# battery_box.net
KiCad netlist of a schematic drawn in EAGLE
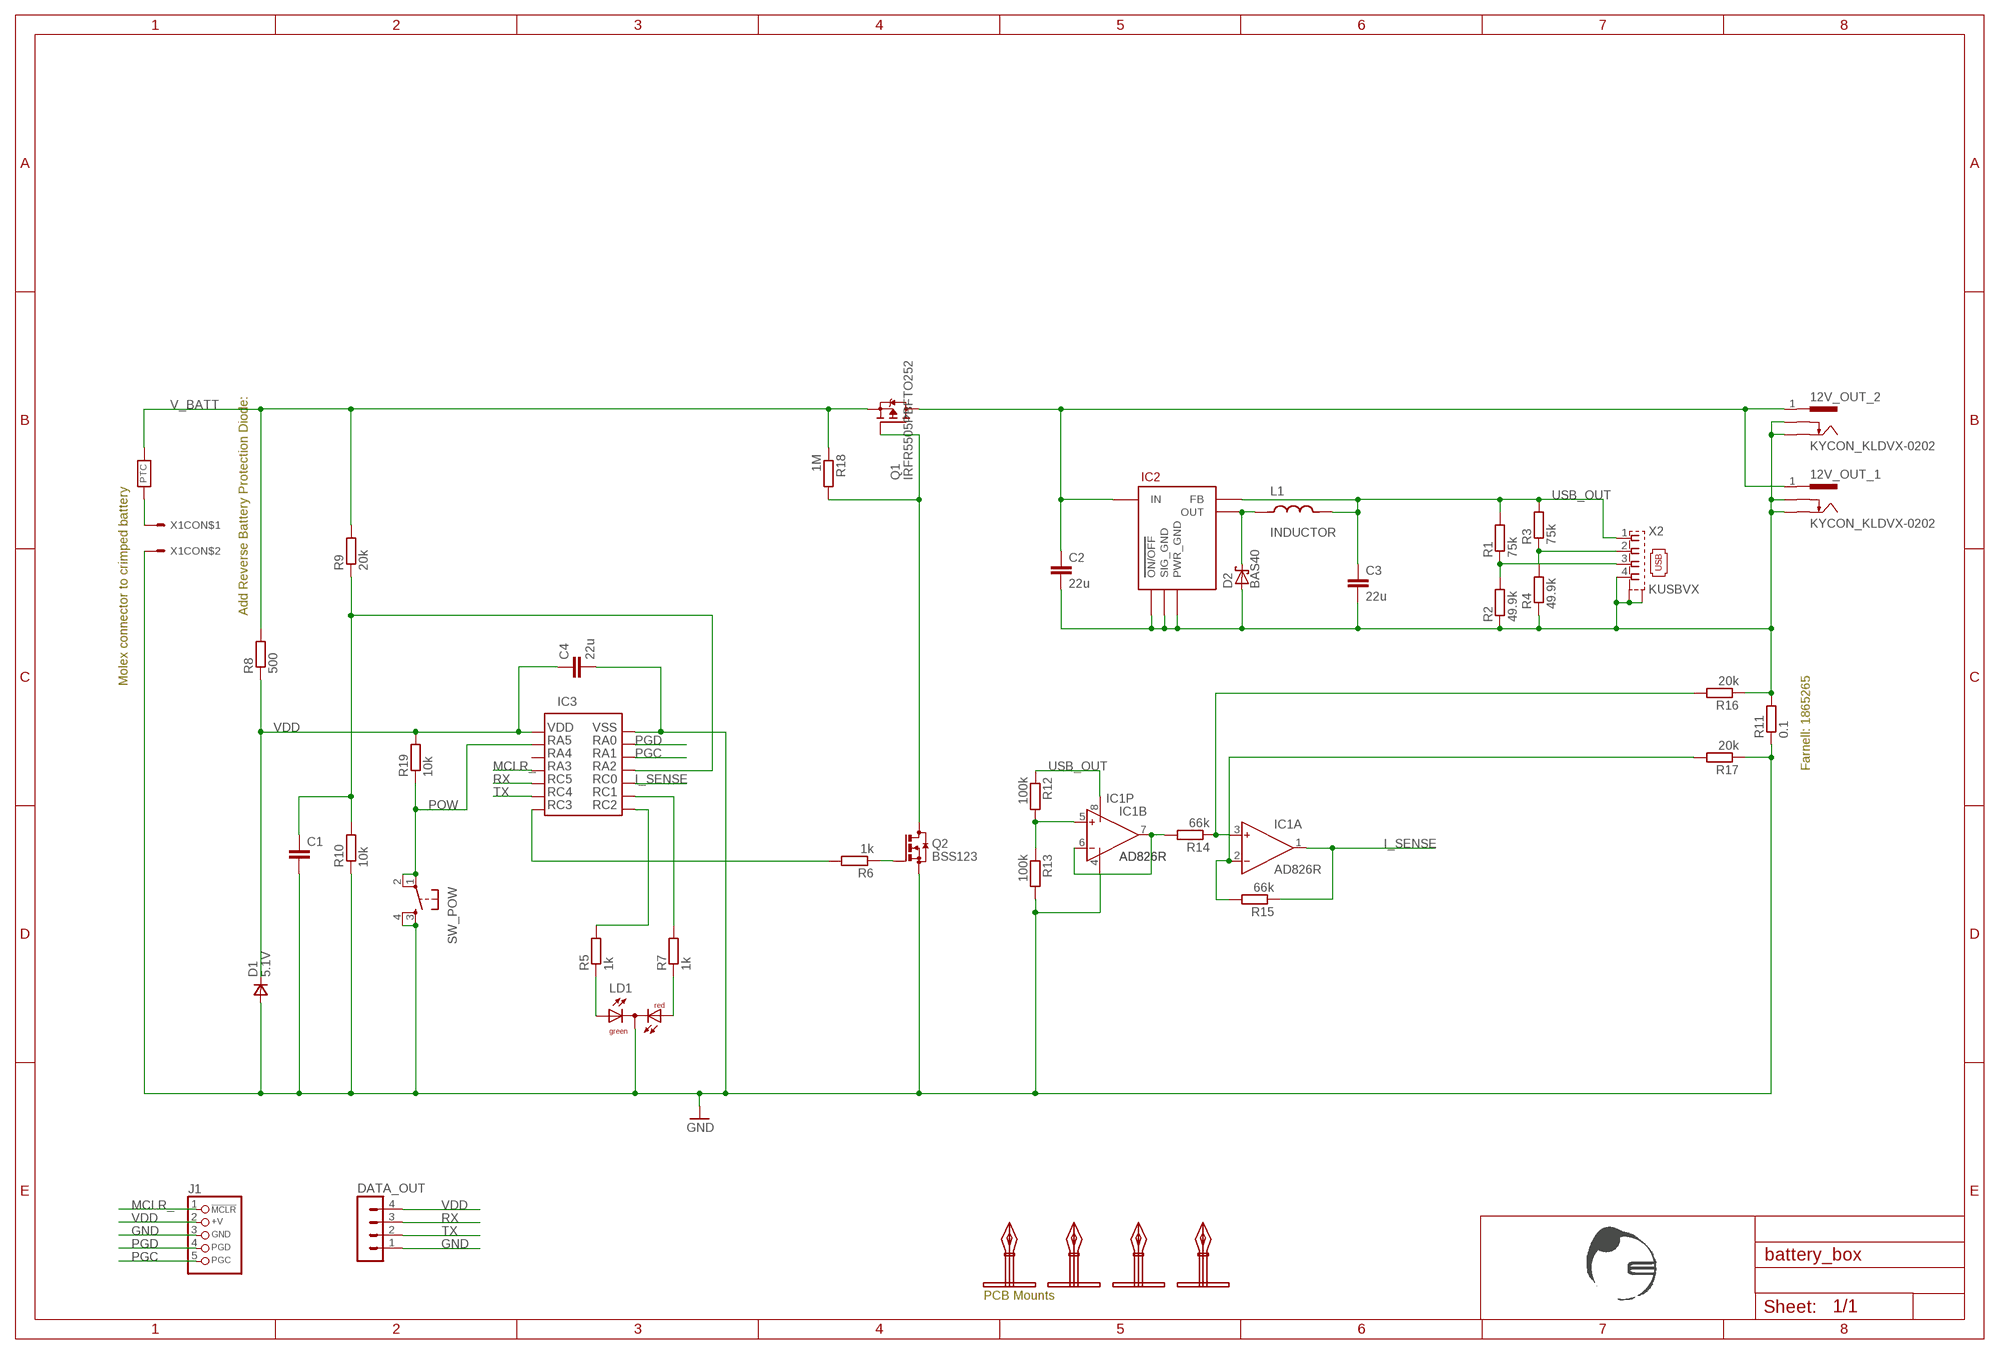
[diagram p0: schematic, sheet 1]

(export (version "E")
  (design (tool "Eeschema 10.0.6"))
  (components
    (comp (ref "12V_OUT_1")
      (value "KYCON_KLDVX-0202")
      (footprint "eagle-import:KYCON_KLVDX_2020_B")
      (libsource (lib "eagle-import") (part "KYCON_KLDVX-0202"))
    )
    (comp (ref "12V_OUT_2")
      (value "KYCON_KLDVX-0202")
      (footprint "eagle-import:KYCON_KLVDX_2020_B")
      (libsource (lib "eagle-import") (part "KYCON_KLDVX-0202"))
    )
    (comp (ref "C1")
      (value "C-EUC0805")
      (footprint "eagle-import:C0805")
      (libsource (lib "eagle-import") (part "C-EUC0805"))
    )
    (comp (ref "C2")
      (value "22u")
      (footprint "eagle-import:C0805")
      (libsource (lib "eagle-import") (part "C-EUC0805"))
    )
    (comp (ref "C3")
      (value "22u")
      (footprint "eagle-import:C0805")
      (libsource (lib "eagle-import") (part "C-EUC0805"))
    )
    (comp (ref "C4")
      (value "22u")
      (footprint "eagle-import:C0805")
      (libsource (lib "eagle-import") (part "C-EUC0805"))
    )
    (comp (ref "D1")
      (value "5.1V")
      (footprint "eagle-import:SOD323")
      (fields (field (name "MPN") "CDSOD323-T05C"))
      (libsource (lib "eagle-import") (part "DSOD323"))
    )
    (comp (ref "D2")
      (value "BAS40")
      (footprint "eagle-import:SOT23")
      (libsource (lib "eagle-import") (part "BAS40"))
    )
    (comp (ref "DATA_OUT")
      (value "MA04-1")
      (footprint "eagle-import:MA04-1")
      (libsource (lib "eagle-import") (part "MA04-1"))
    )
    (comp (ref "IC1")
      (value "AD826R")
      (footprint "eagle-import:SO8")
      (libsource (lib "eagle-import") (part "AD826R"))
    )
    (comp (ref "IC2")
      (value "LM2574")
      (footprint "eagle-import:SO14W")
      (libsource (lib "eagle-import") (part "LM2574"))
    )
    (comp (ref "IC3")
      (value "PIC16F1824")
      (footprint "eagle-import:SO-14")
      (libsource (lib "eagle-import") (part "PIC16F1824"))
    )
    (comp (ref "J1")
      (value "CON_HEADER_PRG_PIC_ICSPA")
      (footprint "eagle-import:HEADER_PRG_1X05")
      (libsource (lib "eagle-import") (part "CON_HEADER_PRG_PIC_ICSPA"))
    )
    (comp (ref "L1")
      (value "INDUCTOR")
      (footprint "eagle-import:SMD_INDUCTOR")
      (libsource (lib "eagle-import") (part "INDUCTOR"))
    )
    (comp (ref "LD1")
      (value "DUOLED-RG-C")
      (footprint "eagle-import:DUOLED-C-5MM")
      (libsource (lib "eagle-import") (part "DUOLED-RG-C"))
    )
    (comp (ref "Q1")
      (value "IRFR5505PBFTO252")
      (footprint "eagle-import:TO252")
      (libsource (lib "eagle-import") (part "IRFR5505PBFTO252"))
    )
    (comp (ref "Q2")
      (value "BSS123")
      (footprint "eagle-import:SOT23")
      (libsource (lib "eagle-import") (part "BSS123"))
    )
    (comp (ref "R1")
      (value "75k")
      (footprint "eagle-import:R0805")
      (libsource (lib "eagle-import") (part "R-EU_R0805"))
    )
    (comp (ref "R2")
      (value "49.9k")
      (footprint "eagle-import:R0805")
      (libsource (lib "eagle-import") (part "R-EU_R0805"))
    )
    (comp (ref "R3")
      (value "75k")
      (footprint "eagle-import:R0805")
      (libsource (lib "eagle-import") (part "R-EU_R0805"))
    )
    (comp (ref "R4")
      (value "49.9k")
      (footprint "eagle-import:R0805")
      (libsource (lib "eagle-import") (part "R-EU_R0805"))
    )
    (comp (ref "R5")
      (value "1k")
      (footprint "eagle-import:R0805")
      (libsource (lib "eagle-import") (part "R-EU_R0805"))
    )
    (comp (ref "R6")
      (value "1k")
      (footprint "eagle-import:R0805")
      (libsource (lib "eagle-import") (part "R-EU_R0805"))
    )
    (comp (ref "R7")
      (value "1k")
      (footprint "eagle-import:R0805")
      (libsource (lib "eagle-import") (part "R-EU_R0805"))
    )
    (comp (ref "R8")
      (value "500")
      (footprint "eagle-import:R0805")
      (libsource (lib "eagle-import") (part "R-EU_R0805"))
    )
    (comp (ref "R9")
      (value "20k")
      (footprint "eagle-import:R0805")
      (libsource (lib "eagle-import") (part "R-EU_R0805"))
    )
    (comp (ref "R10")
      (value "10k")
      (footprint "eagle-import:R0805")
      (libsource (lib "eagle-import") (part "R-EU_R0805"))
    )
    (comp (ref "R11")
      (value "0.1")
      (footprint "eagle-import:R2512")
      (libsource (lib "eagle-import") (part "R-EU_R2512"))
    )
    (comp (ref "R12")
      (value "100k")
      (footprint "eagle-import:R0805")
      (libsource (lib "eagle-import") (part "R-EU_R0805"))
    )
    (comp (ref "R13")
      (value "100k")
      (footprint "eagle-import:R0805")
      (libsource (lib "eagle-import") (part "R-EU_R0805"))
    )
    (comp (ref "R14")
      (value "66k")
      (footprint "eagle-import:R0805")
      (libsource (lib "eagle-import") (part "R-EU_R0805"))
    )
    (comp (ref "R15")
      (value "66k")
      (footprint "eagle-import:R0805")
      (libsource (lib "eagle-import") (part "R-EU_R0805"))
    )
    (comp (ref "R16")
      (value "20k")
      (footprint "eagle-import:R0805")
      (libsource (lib "eagle-import") (part "R-EU_R0805"))
    )
    (comp (ref "R17")
      (value "20k")
      (footprint "eagle-import:R0805")
      (libsource (lib "eagle-import") (part "R-EU_R0805"))
    )
    (comp (ref "R18")
      (value "1M")
      (footprint "eagle-import:R0805")
      (libsource (lib "eagle-import") (part "R-EU_R0805"))
    )
    (comp (ref "R19")
      (value "10k")
      (footprint "eagle-import:R0805")
      (libsource (lib "eagle-import") (part "R-EU_R0805"))
    )
    (comp (ref "SW_POW")
      (value "TAC_SWITCHPTH")
      (footprint "eagle-import:TACTILE-PTH")
      (libsource (lib "eagle-import") (part "TAC_SWITCHPTH"))
    )
    (comp (ref "U$1")
      (value "EQUINOX_LOGO_SMALL")
      (footprint "eagle-import:EQUINOX_LOGO_SMALL")
      (libsource (lib "eagle-import") (part "EQUINOX_LOGO_SMALL"))
    )
    (comp (ref "U$2")
      (value "PTC")
      (footprint "eagle-import:MINISMDC260F")
      (libsource (lib "eagle-import") (part "PTC"))
    )
    (comp (ref "U$5")
      (value "PCB_MOUNT_RICHO")
      (footprint "eagle-import:PCBMOUNT")
      (libsource (lib "eagle-import") (part "PCB_MOUNT_RICHO"))
    )
    (comp (ref "U$6")
      (value "PCB_MOUNT_RICHO")
      (footprint "eagle-import:PCBMOUNT")
      (libsource (lib "eagle-import") (part "PCB_MOUNT_RICHO"))
    )
    (comp (ref "U$7")
      (value "PCB_MOUNT_RICHO")
      (footprint "eagle-import:PCBMOUNT")
      (libsource (lib "eagle-import") (part "PCB_MOUNT_RICHO"))
    )
    (comp (ref "U$8")
      (value "PCB_MOUNT_RICHO")
      (footprint "eagle-import:PCBMOUNT")
      (libsource (lib "eagle-import") (part "PCB_MOUNT_RICHO"))
    )
    (comp (ref "X1")
      (value "CON_MOLEX_39_29_1028")
      (footprint "eagle-import:MOLEX_39_29_1028")
      (libsource (lib "eagle-import") (part "CON_MOLEX_39_29_1028"))
    )
    (comp (ref "X2")
      (value "KUSBVX")
      (footprint "eagle-import:KUSBVX")
      (libsource (lib "eagle-import") (part "KUSBVX"))
    )
  )
  (nets
    (net (code "1") (name "/I_SENSE") (class "Default")
      (node (ref "IC1") (pin "1") (pinfunction "OUT_1") (pintype "output"))
      (node (ref "IC3") (pin "10") (pinfunction "P$10_10") (pintype "bidirectional"))
      (node (ref "R15") (pin "1") (pinfunction "1_1") (pintype "passive"))
    )
    (net (code "2") (name "/MCLR_") (class "Default")
      (node (ref "IC3") (pin "4") (pinfunction "P$4_4") (pintype "bidirectional"))
      (node (ref "J1") (pin "1") (pinfunction "/MCLR_1") (pintype "passive"))
    )
    (net (code "3") (name "/PGC") (class "Default")
      (node (ref "IC3") (pin "12") (pinfunction "P$12_12") (pintype "bidirectional"))
      (node (ref "J1") (pin "5") (pinfunction "PGC_5") (pintype "passive"))
    )
    (net (code "4") (name "/PGD") (class "Default")
      (node (ref "IC3") (pin "13") (pinfunction "P$13_13") (pintype "bidirectional"))
      (node (ref "J1") (pin "4") (pinfunction "PGD_4") (pintype "passive"))
    )
    (net (code "5") (name "/POW") (class "Default")
      (node (ref "IC3") (pin "2") (pinfunction "P$2_2") (pintype "bidirectional"))
      (node (ref "R19") (pin "1") (pinfunction "1_1") (pintype "passive"))
      (node (ref "SW_POW") (pin "1") (pinfunction "1_1") (pintype "passive"))
      (node (ref "SW_POW") (pin "2") (pinfunction "2_2") (pintype "passive"))
    )
    (net (code "6") (name "/RX") (class "Default")
      (node (ref "DATA_OUT") (pin "3") (pinfunction "3_3") (pintype "passive"))
      (node (ref "IC3") (pin "5") (pinfunction "P$5_5") (pintype "bidirectional"))
    )
    (net (code "7") (name "/TX") (class "Default")
      (node (ref "DATA_OUT") (pin "2") (pinfunction "2_2") (pintype "passive"))
      (node (ref "IC3") (pin "6") (pinfunction "P$6_6") (pintype "bidirectional"))
    )
    (net (code "8") (name "/USB_OUT") (class "Default")
      (node (ref "C3") (pin "1") (pinfunction "1_1") (pintype "passive"))
      (node (ref "IC1") (pin "8") (pinfunction "V+_8") (pintype "power_in"))
      (node (ref "IC2") (pin "3") (pinfunction "FB_3") (pintype "bidirectional"))
      (node (ref "L1") (pin "P$2") (pinfunction "P$2_P$2") (pintype "bidirectional"))
      (node (ref "R1") (pin "2") (pinfunction "2_2") (pintype "passive"))
      (node (ref "R12") (pin "1") (pinfunction "1_1") (pintype "passive"))
      (node (ref "R3") (pin "2") (pinfunction "2_2") (pintype "passive"))
      (node (ref "X2") (pin "1") (pinfunction "1_1") (pintype "passive"))
    )
    (net (code "9") (name "/VDD") (class "Default")
      (node (ref "C4") (pin "1") (pinfunction "1_1") (pintype "passive"))
      (node (ref "D1") (pin "1") (pinfunction "C_1") (pintype "passive"))
      (node (ref "DATA_OUT") (pin "4") (pinfunction "4_4") (pintype "passive"))
      (node (ref "IC3") (pin "1") (pinfunction "P$1_1") (pintype "bidirectional"))
      (node (ref "J1") (pin "2") (pinfunction "+V_2") (pintype "passive"))
      (node (ref "R19") (pin "2") (pinfunction "2_2") (pintype "passive"))
      (node (ref "R8") (pin "1") (pinfunction "1_1") (pintype "passive"))
    )
    (net (code "10") (name "/V_BATT") (class "Default")
      (node (ref "Q1") (pin "2") (pinfunction "S_2") (pintype "passive"))
      (node (ref "R18") (pin "1") (pinfunction "1_1") (pintype "passive"))
      (node (ref "R8") (pin "2") (pinfunction "2_2") (pintype "passive"))
      (node (ref "R9") (pin "2") (pinfunction "2_2") (pintype "passive"))
      (node (ref "U$2") (pin "P$2") (pinfunction "P$2_P$2") (pintype "bidirectional"))
    )
    (net (code "11") (name "GND") (class "Default")
      (node (ref "C1") (pin "2") (pinfunction "2_2") (pintype "passive"))
      (node (ref "C4") (pin "2") (pinfunction "2_2") (pintype "passive"))
      (node (ref "D1") (pin "2") (pinfunction "A_2") (pintype "passive"))
      (node (ref "DATA_OUT") (pin "1") (pinfunction "1_1") (pintype "passive"))
      (node (ref "IC1") (pin "4") (pinfunction "V-_4") (pintype "power_in"))
      (node (ref "IC3") (pin "14") (pinfunction "P$14_14") (pintype "bidirectional"))
      (node (ref "J1") (pin "3") (pinfunction "GND_3") (pintype "passive"))
      (node (ref "LD1") (pin "C") (pinfunction "C_C") (pintype "passive"))
      (node (ref "Q2") (pin "2") (pinfunction "S_2") (pintype "passive"))
      (node (ref "R10") (pin "1") (pinfunction "1_1") (pintype "passive"))
      (node (ref "R11") (pin "1") (pinfunction "1_1") (pintype "passive"))
      (node (ref "R13") (pin "2") (pinfunction "2_2") (pintype "passive"))
      (node (ref "R17") (pin "1") (pinfunction "1_1") (pintype "passive"))
      (node (ref "SW_POW") (pin "3") (pinfunction "3_3") (pintype "passive"))
      (node (ref "SW_POW") (pin "4") (pinfunction "4_4") (pintype "passive"))
      (node (ref "X1") (pin "P$2") (pinfunction "S_P$2") (pintype "passive"))
    )
    (net (code "12") (name "Net-(12V_OUT_1-PAD1)") (class "Default")
      (node (ref "12V_OUT_1") (pin "1") (pinfunction "PAD1_1") (pintype "passive"))
      (node (ref "12V_OUT_2") (pin "1") (pinfunction "PAD1_1") (pintype "passive"))
      (node (ref "C2") (pin "1") (pinfunction "1_1") (pintype "passive"))
      (node (ref "IC2") (pin "10") (pinfunction "IN_10") (pintype "bidirectional"))
      (node (ref "Q1") (pin "3") (pinfunction "D_3") (pintype "passive"))
    )
    (net (code "13") (name "Net-(12V_OUT_1-PAD2)") (class "Default")
      (node (ref "12V_OUT_1") (pin "2") (pinfunction "PAD2_2") (pintype "passive"))
      (node (ref "12V_OUT_1") (pin "3") (pinfunction "PAD3_3") (pintype "passive"))
      (node (ref "12V_OUT_2") (pin "2") (pinfunction "PAD2_2") (pintype "passive"))
      (node (ref "12V_OUT_2") (pin "3") (pinfunction "PAD3_3") (pintype "passive"))
      (node (ref "C2") (pin "2") (pinfunction "2_2") (pintype "passive"))
      (node (ref "C3") (pin "2") (pinfunction "2_2") (pintype "passive"))
      (node (ref "D2") (pin "1") (pinfunction "A_1") (pintype "passive"))
      (node (ref "IC2") (pin "4") (pinfunction "SIG_GND_4") (pintype "bidirectional"))
      (node (ref "IC2") (pin "5") (pinfunction "ON/OFF_5") (pintype "bidirectional"))
      (node (ref "IC2") (pin "6") (pinfunction "PWR_GND_6") (pintype "bidirectional"))
      (node (ref "R11") (pin "2") (pinfunction "2_2") (pintype "passive"))
      (node (ref "R16") (pin "1") (pinfunction "1_1") (pintype "passive"))
      (node (ref "R2") (pin "1") (pinfunction "1_1") (pintype "passive"))
      (node (ref "R4") (pin "1") (pinfunction "1_1") (pintype "passive"))
      (node (ref "X2") (pin "4") (pinfunction "4_4") (pintype "passive"))
      (node (ref "X2") (pin "M1") (pinfunction "S1_M1") (pintype "passive"))
      (node (ref "X2") (pin "M2") (pinfunction "S2_M2") (pintype "passive"))
    )
    (net (code "14") (name "Net-(D2-C)") (class "Default")
      (node (ref "D2") (pin "3") (pinfunction "C_3") (pintype "passive"))
      (node (ref "IC2") (pin "12") (pinfunction "OUT_12") (pintype "bidirectional"))
      (node (ref "L1") (pin "P$1") (pinfunction "P$1_P$1") (pintype "bidirectional"))
    )
    (net (code "15") (name "Net-(IC1A-IN+)") (class "Default")
      (node (ref "IC1") (pin "3") (pinfunction "IN+_3") (pintype "input"))
      (node (ref "R14") (pin "1") (pinfunction "1_1") (pintype "passive"))
      (node (ref "R16") (pin "2") (pinfunction "2_2") (pintype "passive"))
    )
    (net (code "16") (name "Net-(IC1A-IN-)") (class "Default")
      (node (ref "IC1") (pin "2") (pinfunction "IN-_2") (pintype "input"))
      (node (ref "R15") (pin "2") (pinfunction "2_2") (pintype "passive"))
      (node (ref "R17") (pin "2") (pinfunction "2_2") (pintype "passive"))
    )
    (net (code "17") (name "Net-(IC1B-IN+)") (class "Default")
      (node (ref "IC1") (pin "5") (pinfunction "IN+_5") (pintype "input"))
      (node (ref "R12") (pin "2") (pinfunction "2_2") (pintype "passive"))
      (node (ref "R13") (pin "1") (pinfunction "1_1") (pintype "passive"))
    )
    (net (code "18") (name "Net-(IC1B-IN-)") (class "Default")
      (node (ref "IC1") (pin "6") (pinfunction "IN-_6") (pintype "input"))
      (node (ref "IC1") (pin "7") (pinfunction "OUT_7") (pintype "output"))
      (node (ref "R14") (pin "2") (pinfunction "2_2") (pintype "passive"))
    )
    (net (code "19") (name "Net-(IC3-P$7)") (class "Default")
      (node (ref "IC3") (pin "7") (pinfunction "P$7_7") (pintype "bidirectional"))
      (node (ref "R6") (pin "2") (pinfunction "2_2") (pintype "passive"))
    )
    (net (code "20") (name "Net-(IC3-P$8)") (class "Default")
      (node (ref "IC3") (pin "8") (pinfunction "P$8_8") (pintype "bidirectional"))
      (node (ref "R5") (pin "2") (pinfunction "2_2") (pintype "passive"))
    )
    (net (code "21") (name "Net-(IC3-P$9)") (class "Default")
      (node (ref "IC3") (pin "9") (pinfunction "P$9_9") (pintype "bidirectional"))
      (node (ref "R7") (pin "2") (pinfunction "2_2") (pintype "passive"))
    )
    (net (code "22") (name "Net-(IC3-P$11)") (class "Default")
      (node (ref "C1") (pin "1") (pinfunction "1_1") (pintype "passive"))
      (node (ref "IC3") (pin "11") (pinfunction "P$11_11") (pintype "bidirectional"))
      (node (ref "R10") (pin "2") (pinfunction "2_2") (pintype "passive"))
      (node (ref "R9") (pin "1") (pinfunction "1_1") (pintype "passive"))
    )
    (net (code "23") (name "Net-(LD1-AG)") (class "Default")
      (node (ref "LD1") (pin "AX") (pinfunction "AG_AX") (pintype "passive"))
      (node (ref "R5") (pin "1") (pinfunction "1_1") (pintype "passive"))
    )
    (net (code "24") (name "Net-(LD1-PadAR)") (class "Default")
      (node (ref "LD1") (pin "AR") (pinfunction "AR_AR") (pintype "passive"))
      (node (ref "R7") (pin "1") (pinfunction "1_1") (pintype "passive"))
    )
    (net (code "25") (name "Net-(Q1-G)") (class "Default")
      (node (ref "Q1") (pin "1") (pinfunction "G_1") (pintype "passive"))
      (node (ref "Q2") (pin "3") (pinfunction "D_3") (pintype "passive"))
      (node (ref "R18") (pin "2") (pinfunction "2_2") (pintype "passive"))
    )
    (net (code "26") (name "Net-(Q2-G)") (class "Default")
      (node (ref "Q2") (pin "1") (pinfunction "G_1") (pintype "passive"))
      (node (ref "R6") (pin "1") (pinfunction "1_1") (pintype "passive"))
    )
    (net (code "27") (name "Net-(R1-Pad1)") (class "Default")
      (node (ref "R1") (pin "1") (pinfunction "1_1") (pintype "passive"))
      (node (ref "R2") (pin "2") (pinfunction "2_2") (pintype "passive"))
      (node (ref "X2") (pin "3") (pinfunction "3_3") (pintype "passive"))
    )
    (net (code "28") (name "Net-(R3-Pad1)") (class "Default")
      (node (ref "R3") (pin "1") (pinfunction "1_1") (pintype "passive"))
      (node (ref "R4") (pin "2") (pinfunction "2_2") (pintype "passive"))
      (node (ref "X2") (pin "2") (pinfunction "2_2") (pintype "passive"))
    )
    (net (code "29") (name "Net-(X1A-S)") (class "Default")
      (node (ref "U$2") (pin "P$1") (pinfunction "P$1_P$1") (pintype "bidirectional"))
      (node (ref "X1") (pin "P$1") (pinfunction "S_P$1") (pintype "passive"))
    )
    (net (code "30") (name "unconnected-(IC3-P$3-Pad3)") (class "Default")
      (node (ref "IC3") (pin "3") (pinfunction "P$3_3") (pintype "bidirectional"))
    )
  )
)
